# osbo_v11.net
KiCad netlist of a schematic drawn in EAGLE
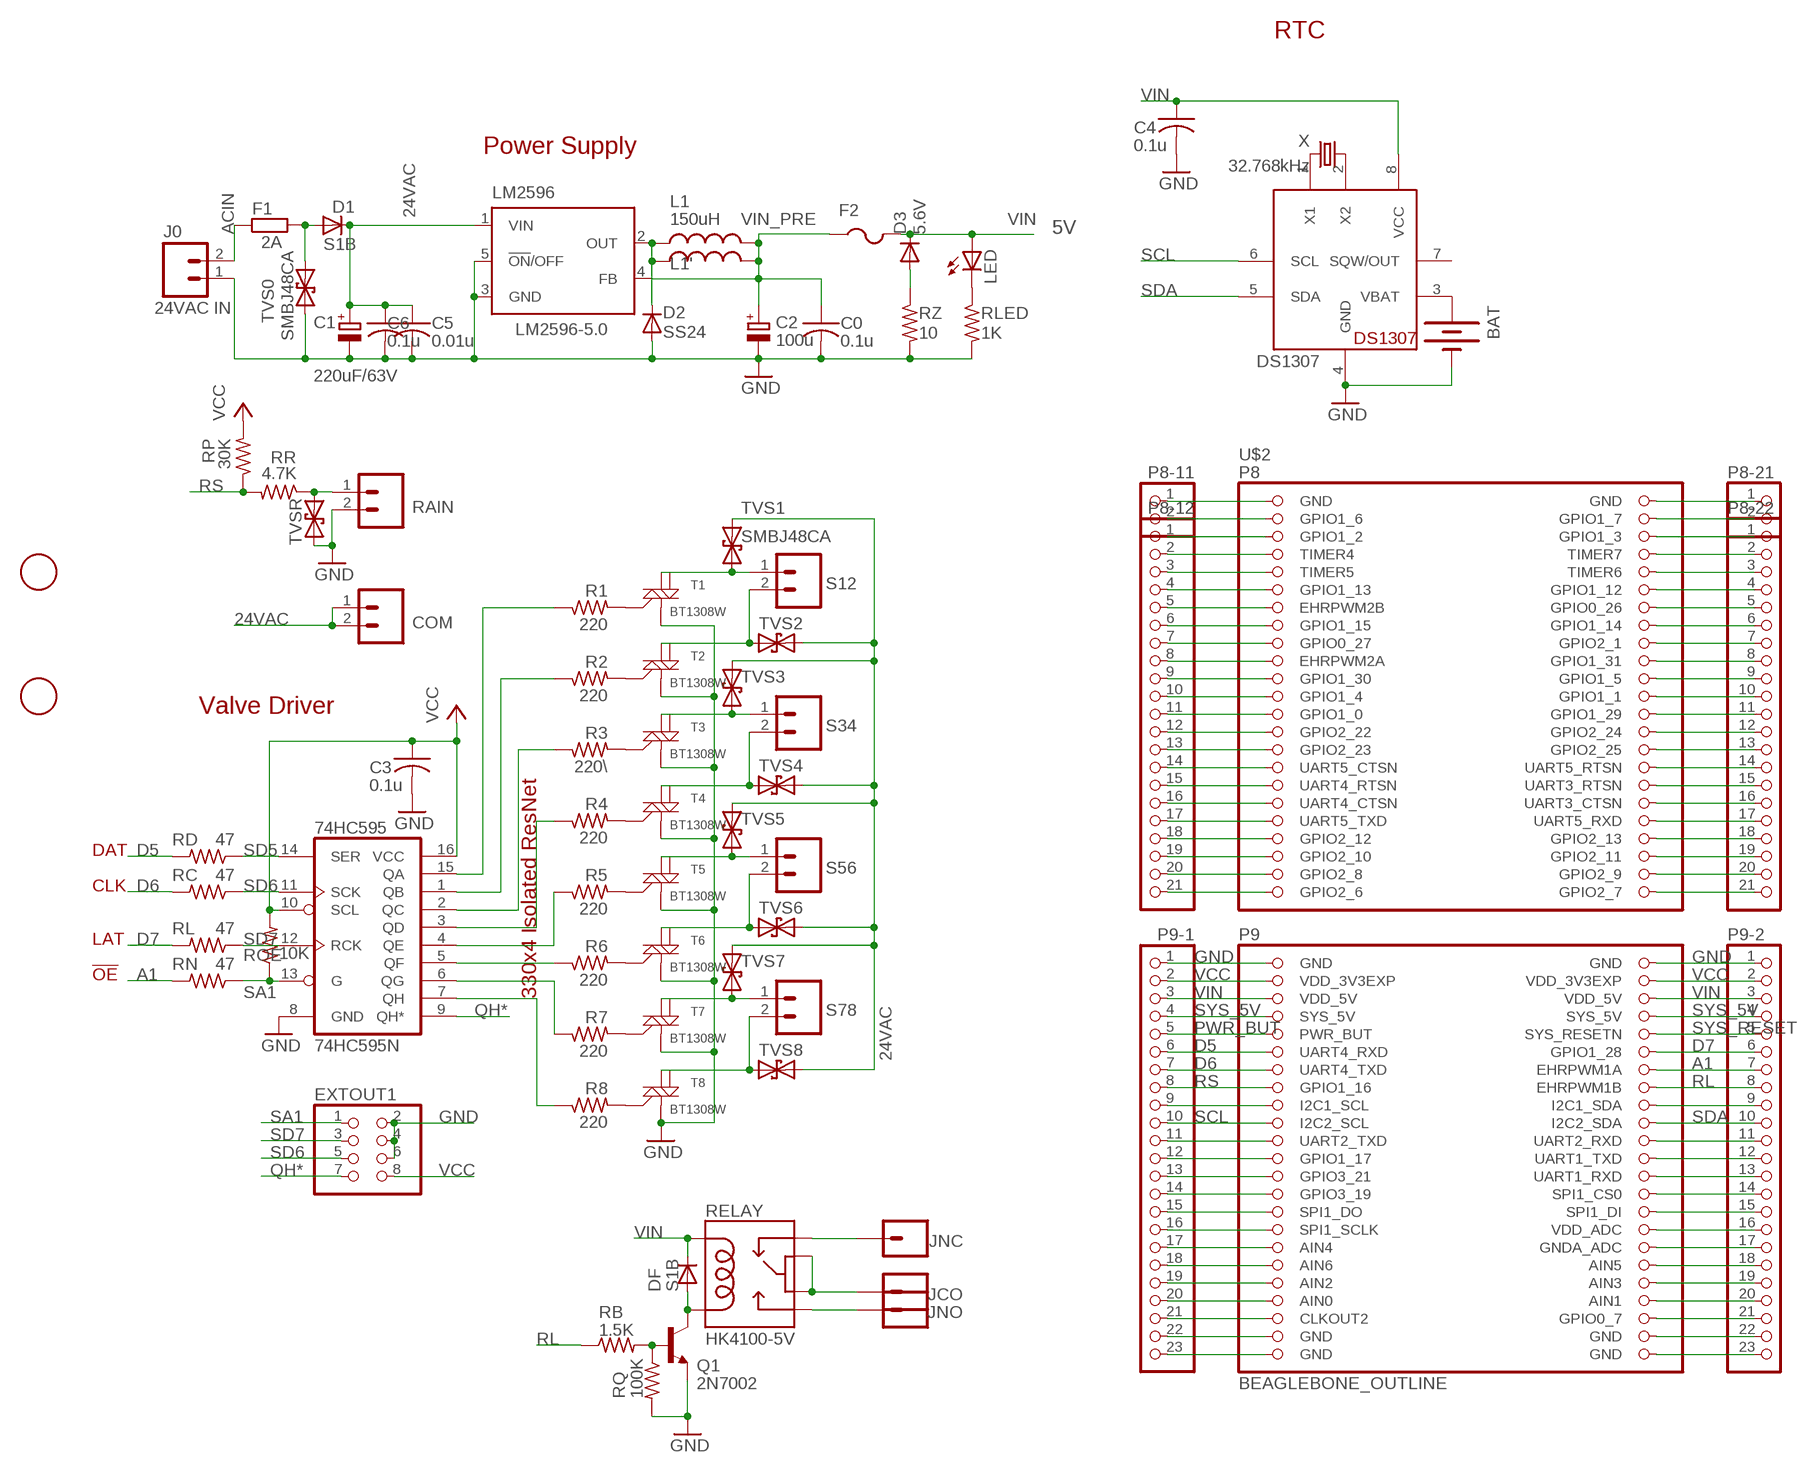
[diagram p0: schematic, sheet 1]

(export (version "E")
  (design (tool "Eeschema 10.0.6"))
  (components
    (comp (ref "74HC595")
      (value "74HC595N")
      (footprint "eagle-import:SO16")
      (libsource (lib "eagle-import") (part "74595DLS"))
    )
    (comp (ref "BAT")
      (value "BATTERYBATTERY_12MM_SMT")
      (footprint "eagle-import:BATTCON_12MM_SMT")
      (libsource (lib "eagle-import") (part "BATTERYBATTERY_12MM_SMT"))
    )
    (comp (ref "C0")
      (value "0.1u")
      (footprint "eagle-import:C0805K")
      (libsource (lib "eagle-import") (part "C-USC0805K"))
    )
    (comp (ref "C1")
      (value "220uF/63V")
      (footprint "eagle-import:E5-10.5-1")
      (libsource (lib "eagle-import") (part "CPOL-EUE5-10.5-1"))
    )
    (comp (ref "C2")
      (value "100u")
      (footprint "eagle-import:E3,5-8")
      (libsource (lib "eagle-import") (part "CPOL-EUE3.5-8"))
    )
    (comp (ref "C3")
      (value "0.1u")
      (footprint "eagle-import:C0805K")
      (libsource (lib "eagle-import") (part "C-USC0805K"))
    )
    (comp (ref "C4")
      (value "0.1u")
      (footprint "eagle-import:C0805K")
      (libsource (lib "eagle-import") (part "C-USC0805K"))
    )
    (comp (ref "C5")
      (value "0.01u")
      (footprint "eagle-import:C0805K")
      (libsource (lib "eagle-import") (part "C-USC0805K"))
    )
    (comp (ref "C6")
      (value "0.1u")
      (footprint "eagle-import:C0805K")
      (libsource (lib "eagle-import") (part "C-USC0805K"))
    )
    (comp (ref "COM")
      (value "M025MM-X")
      (footprint "eagle-import:SCREWTERMINAL-5MM-2-X")
      (libsource (lib "eagle-import") (part "M025MM-X"))
    )
    (comp (ref "D1")
      (value "S1B")
      (footprint "eagle-import:DO-214AC")
      (libsource (lib "eagle-import") (part "DIODE-DO-214AC"))
    )
    (comp (ref "D2")
      (value "SS24")
      (footprint "eagle-import:SMB")
      (libsource (lib "eagle-import") (part "DIODE-SMB"))
    )
    (comp (ref "D3")
      (value "5.6V")
      (footprint "eagle-import:MINIMELF")
      (libsource (lib "eagle-import") (part "DIODE-MINIMELF"))
    )
    (comp (ref "DF")
      (value "S1B")
      (footprint "eagle-import:DO-214AC")
      (libsource (lib "eagle-import") (part "DIODE-DO-214AC"))
    )
    (comp (ref "DS1307")
      (value "DS1307")
      (footprint "eagle-import:SO08")
      (libsource (lib "eagle-import") (part "DS1307SOIC"))
    )
    (comp (ref "EXTOUT1")
      (value "PINHD-2X4/90")
      (footprint "eagle-import:2X04_90")
      (libsource (lib "eagle-import") (part "PINHD-2X4/90"))
    )
    (comp (ref "F1")
      (value "2A")
      (footprint "eagle-import:0411V")
      (libsource (lib "eagle-import") (part "R-EU_0411/3V"))
    )
    (comp (ref "F2")
      (value "PTCFUSE-1812")
      (footprint "eagle-import:1812")
      (libsource (lib "eagle-import") (part "PTCFUSE-1812"))
    )
    (comp (ref "J0")
      (value "24VAC IN")
      (footprint "eagle-import:SCREWTERMINAL-4MM-2-X")
      (libsource (lib "eagle-import") (part "M024MM-X"))
    )
    (comp (ref "JCO")
      (value "M01PTH")
      (footprint "eagle-import:1X01")
      (libsource (lib "eagle-import") (part "M01PTH"))
    )
    (comp (ref "JNC")
      (value "M01PTH")
      (footprint "eagle-import:1X01")
      (libsource (lib "eagle-import") (part "M01PTH"))
    )
    (comp (ref "JNO")
      (value "M01PTH")
      (footprint "eagle-import:1X01")
      (libsource (lib "eagle-import") (part "M01PTH"))
    )
    (comp (ref "L1")
      (value "150uH")
      (footprint "eagle-import:CDRH125")
      (libsource (lib "eagle-import") (part "INDUCTORPWR"))
    )
    (comp (ref "L1'")
      (value "150uH")
      (footprint "eagle-import:0207_7")
      (libsource (lib "eagle-import") (part "L-US0207/7"))
    )
    (comp (ref "LED")
      (value "LEDCHIPLED_0805")
      (footprint "eagle-import:CHIPLED_0805")
      (libsource (lib "eagle-import") (part "LEDCHIPLED_0805"))
    )
    (comp (ref "LM2596")
      (value "LM2596-5.0")
      (footprint "eagle-import:TO263-5")
      (fields (field (name "MF") "NATIONAL SEMICONDUCTOR") (field (name "MPN") "LM2596S-ADJ/NOPB"))
      (libsource (lib "eagle-import") (part "LM2596S"))
    )
    (comp (ref "P8-11")
      (value "PINHD-1X2")
      (footprint "eagle-import:1X02")
      (libsource (lib "eagle-import") (part "PINHD-1X2"))
    )
    (comp (ref "P8-12")
      (value "PINHD-1X21")
      (footprint "eagle-import:1X21")
      (libsource (lib "eagle-import") (part "PINHD-1X21"))
    )
    (comp (ref "P8-21")
      (value "PINHD-1X2")
      (footprint "eagle-import:1X02")
      (libsource (lib "eagle-import") (part "PINHD-1X2"))
    )
    (comp (ref "P8-22")
      (value "PINHD-1X21")
      (footprint "eagle-import:1X21")
      (libsource (lib "eagle-import") (part "PINHD-1X21"))
    )
    (comp (ref "P9-1")
      (value "PINHD-1X23")
      (footprint "eagle-import:1X23")
      (libsource (lib "eagle-import") (part "PINHD-1X23"))
    )
    (comp (ref "P9-2")
      (value "PINHD-1X23")
      (footprint "eagle-import:1X23")
      (libsource (lib "eagle-import") (part "PINHD-1X23"))
    )
    (comp (ref "Q1")
      (value "2N7002")
      (footprint "eagle-import:SOT23-3")
      (libsource (lib "eagle-import") (part "TRANSISTOR_NPNSOT23-3"))
    )
    (comp (ref "R1")
      (value "220")
      (footprint "eagle-import:R0805")
      (libsource (lib "eagle-import") (part "R-US_R0805"))
    )
    (comp (ref "R2")
      (value "220")
      (footprint "eagle-import:R0805")
      (libsource (lib "eagle-import") (part "R-US_R0805"))
    )
    (comp (ref "R3")
      (value "220\\")
      (footprint "eagle-import:R0805")
      (libsource (lib "eagle-import") (part "R-US_R0805"))
    )
    (comp (ref "R4")
      (value "220")
      (footprint "eagle-import:R0805")
      (libsource (lib "eagle-import") (part "R-US_R0805"))
    )
    (comp (ref "R5")
      (value "220")
      (footprint "eagle-import:R0805")
      (libsource (lib "eagle-import") (part "R-US_R0805"))
    )
    (comp (ref "R6")
      (value "220")
      (footprint "eagle-import:R0805")
      (libsource (lib "eagle-import") (part "R-US_R0805"))
    )
    (comp (ref "R7")
      (value "220")
      (footprint "eagle-import:R0805")
      (libsource (lib "eagle-import") (part "R-US_R0805"))
    )
    (comp (ref "R8")
      (value "220")
      (footprint "eagle-import:R0805")
      (libsource (lib "eagle-import") (part "R-US_R0805"))
    )
    (comp (ref "RAIN")
      (value "M025MM-X")
      (footprint "eagle-import:SCREWTERMINAL-5MM-2-X")
      (libsource (lib "eagle-import") (part "M025MM-X"))
    )
    (comp (ref "RB")
      (value "1.5K")
      (footprint "eagle-import:R0805")
      (libsource (lib "eagle-import") (part "R-US_R0805"))
    )
    (comp (ref "RC")
      (value "47")
      (footprint "eagle-import:R0805")
      (libsource (lib "eagle-import") (part "R-US_R0805"))
    )
    (comp (ref "RD")
      (value "47")
      (footprint "eagle-import:R0805")
      (libsource (lib "eagle-import") (part "R-US_R0805"))
    )
    (comp (ref "RELAY")
      (value "HK4100-5V")
      (footprint "eagle-import:RELAY-HK4100F")
      (libsource (lib "eagle-import") (part "RELAY-2"))
    )
    (comp (ref "RL")
      (value "47")
      (footprint "eagle-import:R0805")
      (libsource (lib "eagle-import") (part "R-US_R0805"))
    )
    (comp (ref "RLED")
      (value "1K")
      (footprint "eagle-import:R0805")
      (libsource (lib "eagle-import") (part "R-US_R0805"))
    )
    (comp (ref "RN")
      (value "47")
      (footprint "eagle-import:R0805")
      (libsource (lib "eagle-import") (part "R-US_R0805"))
    )
    (comp (ref "ROE")
      (value "10K")
      (footprint "eagle-import:R0805")
      (libsource (lib "eagle-import") (part "R-US_R0805"))
    )
    (comp (ref "RP")
      (value "30K")
      (footprint "eagle-import:R0805")
      (libsource (lib "eagle-import") (part "R-US_R0805"))
    )
    (comp (ref "RQ")
      (value "100K")
      (footprint "eagle-import:R0805")
      (libsource (lib "eagle-import") (part "R-US_R0805"))
    )
    (comp (ref "RR")
      (value "4.7K")
      (footprint "eagle-import:R0805")
      (libsource (lib "eagle-import") (part "R-US_R0805"))
    )
    (comp (ref "RZ")
      (value "10")
      (footprint "eagle-import:R0805")
      (libsource (lib "eagle-import") (part "R-US_R0805"))
    )
    (comp (ref "S12")
      (value "M025MM-X")
      (footprint "eagle-import:SCREWTERMINAL-5MM-2-X")
      (libsource (lib "eagle-import") (part "M025MM-X"))
    )
    (comp (ref "S34")
      (value "M025MM-X")
      (footprint "eagle-import:SCREWTERMINAL-5MM-2-X")
      (libsource (lib "eagle-import") (part "M025MM-X"))
    )
    (comp (ref "S56")
      (value "M025MM-X")
      (footprint "eagle-import:SCREWTERMINAL-5MM-2-X")
      (libsource (lib "eagle-import") (part "M025MM-X"))
    )
    (comp (ref "S78")
      (value "M025MM-X")
      (footprint "eagle-import:SCREWTERMINAL-5MM-2-X")
      (libsource (lib "eagle-import") (part "M025MM-X"))
    )
    (comp (ref "T1")
      (value "BT1308W")
      (footprint "eagle-import:SOT223")
      (libsource (lib "eagle-import") (part "MAC97SOT223"))
    )
    (comp (ref "T2")
      (value "BT1308W")
      (footprint "eagle-import:SOT223")
      (libsource (lib "eagle-import") (part "MAC97SOT223"))
    )
    (comp (ref "T3")
      (value "BT1308W")
      (footprint "eagle-import:SOT223")
      (libsource (lib "eagle-import") (part "MAC97SOT223"))
    )
    (comp (ref "T4")
      (value "BT1308W")
      (footprint "eagle-import:SOT223")
      (libsource (lib "eagle-import") (part "MAC97SOT223"))
    )
    (comp (ref "T5")
      (value "BT1308W")
      (footprint "eagle-import:SOT223")
      (libsource (lib "eagle-import") (part "MAC97SOT223"))
    )
    (comp (ref "T6")
      (value "BT1308W")
      (footprint "eagle-import:SOT223")
      (libsource (lib "eagle-import") (part "MAC97SOT223"))
    )
    (comp (ref "T7")
      (value "BT1308W")
      (footprint "eagle-import:SOT223")
      (libsource (lib "eagle-import") (part "MAC97SOT223"))
    )
    (comp (ref "T8")
      (value "BT1308W")
      (footprint "eagle-import:SOT223")
      (libsource (lib "eagle-import") (part "MAC97SOT223"))
    )
    (comp (ref "TVS0")
      (value "SMBJ48CA")
      (footprint "eagle-import:SMB")
      (libsource (lib "eagle-import") (part "TVSSMB"))
    )
    (comp (ref "TVS1")
      (value "SMBJ48CA")
      (footprint "eagle-import:SMB")
      (libsource (lib "eagle-import") (part "TVSSMB"))
    )
    (comp (ref "TVS2")
      (value "TVSSMB")
      (footprint "eagle-import:SMB")
      (libsource (lib "eagle-import") (part "TVSSMB"))
    )
    (comp (ref "TVS3")
      (value "TVSSMB")
      (footprint "eagle-import:SMB")
      (libsource (lib "eagle-import") (part "TVSSMB"))
    )
    (comp (ref "TVS4")
      (value "TVSSMB")
      (footprint "eagle-import:SMB")
      (libsource (lib "eagle-import") (part "TVSSMB"))
    )
    (comp (ref "TVS5")
      (value "TVSSMB")
      (footprint "eagle-import:SMB")
      (libsource (lib "eagle-import") (part "TVSSMB"))
    )
    (comp (ref "TVS6")
      (value "TVSSMB")
      (footprint "eagle-import:SMB")
      (libsource (lib "eagle-import") (part "TVSSMB"))
    )
    (comp (ref "TVS7")
      (value "TVSSMB")
      (footprint "eagle-import:SMB")
      (libsource (lib "eagle-import") (part "TVSSMB"))
    )
    (comp (ref "TVS8")
      (value "TVSSMB")
      (footprint "eagle-import:SMB")
      (libsource (lib "eagle-import") (part "TVSSMB"))
    )
    (comp (ref "TVSR")
      (value "TVSSMB")
      (footprint "eagle-import:SMB")
      (libsource (lib "eagle-import") (part "TVSSMB"))
    )
    (comp (ref "U$1")
      (value "FIDUCIAL")
      (footprint "eagle-import:FIDUCIAL_1MM")
      (libsource (lib "eagle-import") (part "FIDUCIAL"))
    )
    (comp (ref "U$2")
      (value "BEAGLEBONE_OUTLINE")
      (footprint "eagle-import:BEAGLEBONE_SHIELD")
      (libsource (lib "eagle-import") (part "BEAGLEBONE_OUTLINE"))
    )
    (comp (ref "U$3")
      (value "FIDUCIAL")
      (footprint "eagle-import:FIDUCIAL_1MM")
      (libsource (lib "eagle-import") (part "FIDUCIAL"))
    )
    (comp (ref "X")
      (value "32.768kHz")
      (footprint "eagle-import:TC38H")
      (libsource (lib "eagle-import") (part "CRYSTALTC38H"))
    )
  )
  (nets
    (net (code "1") (name "/24VAC") (class "Default")
      (node (ref "COM") (pin "1") (pinfunction "1_1") (pintype "passive"))
      (node (ref "COM") (pin "2") (pinfunction "2_2") (pintype "passive"))
      (node (ref "D1") (pin "A") (pinfunction "A_A") (pintype "passive"))
      (node (ref "F1") (pin "2") (pinfunction "2_2") (pintype "passive"))
      (node (ref "TVS0") (pin "C") (pinfunction "C_C") (pintype "passive"))
      (node (ref "TVS1") (pin "C") (pinfunction "C_C") (pintype "passive"))
      (node (ref "TVS2") (pin "C") (pinfunction "C_C") (pintype "passive"))
      (node (ref "TVS3") (pin "C") (pinfunction "C_C") (pintype "passive"))
      (node (ref "TVS4") (pin "C") (pinfunction "C_C") (pintype "passive"))
      (node (ref "TVS5") (pin "C") (pinfunction "C_C") (pintype "passive"))
      (node (ref "TVS6") (pin "C") (pinfunction "C_C") (pintype "passive"))
      (node (ref "TVS7") (pin "C") (pinfunction "C_C") (pintype "passive"))
      (node (ref "TVS8") (pin "C") (pinfunction "C_C") (pintype "passive"))
    )
    (net (code "2") (name "/A1") (class "Default")
      (node (ref "P9-2") (pin "7") (pinfunction "7_7") (pintype "passive"))
      (node (ref "RN") (pin "2") (pinfunction "2_2") (pintype "passive"))
      (node (ref "U$2") (pin "60") (pinfunction "EHRPWM1A_60") (pintype "passive"))
    )
    (net (code "3") (name "/ACIN") (class "Default")
      (node (ref "F1") (pin "1") (pinfunction "1_1") (pintype "passive"))
      (node (ref "J0") (pin "2") (pinfunction "2_2") (pintype "passive"))
    )
    (net (code "4") (name "/D5") (class "Default")
      (node (ref "P9-1") (pin "6") (pinfunction "6_6") (pintype "passive"))
      (node (ref "RD") (pin "2") (pinfunction "2_2") (pintype "passive"))
      (node (ref "U$2") (pin "57") (pinfunction "UART4_RXD_57") (pintype "passive"))
    )
    (net (code "5") (name "/D6") (class "Default")
      (node (ref "P9-1") (pin "7") (pinfunction "7_7") (pintype "passive"))
      (node (ref "RC") (pin "2") (pinfunction "2_2") (pintype "passive"))
      (node (ref "U$2") (pin "59") (pinfunction "UART4_TXD_59") (pintype "passive"))
    )
    (net (code "6") (name "/D7") (class "Default")
      (node (ref "P9-2") (pin "6") (pinfunction "6_6") (pintype "passive"))
      (node (ref "RL") (pin "2") (pinfunction "2_2") (pintype "passive"))
      (node (ref "U$2") (pin "58") (pinfunction "GPIO1_28_58") (pintype "passive"))
    )
    (net (code "7") (name "/PWR_BUT") (class "Default")
      (node (ref "P9-1") (pin "5") (pinfunction "5_5") (pintype "passive"))
      (node (ref "U$2") (pin "55") (pinfunction "PWR_BUT_55") (pintype "passive"))
    )
    (net (code "8") (name "/QH*") (class "Default")
      (node (ref "74HC595") (pin "9") (pinfunction "QH*_9") (pintype "tri_state"))
      (node (ref "EXTOUT1") (pin "7") (pinfunction "7_7") (pintype "passive"))
    )
    (net (code "9") (name "/RL") (class "Default")
      (node (ref "P9-2") (pin "8") (pinfunction "8_8") (pintype "passive"))
      (node (ref "RB") (pin "1") (pinfunction "1_1") (pintype "passive"))
      (node (ref "U$2") (pin "62") (pinfunction "EHRPWM1B_62") (pintype "passive"))
    )
    (net (code "10") (name "/RS") (class "Default")
      (node (ref "P9-1") (pin "8") (pinfunction "8_8") (pintype "passive"))
      (node (ref "RP") (pin "1") (pinfunction "1_1") (pintype "passive"))
      (node (ref "RR") (pin "2") (pinfunction "2_2") (pintype "passive"))
      (node (ref "U$2") (pin "61") (pinfunction "GPIO1_16_61") (pintype "passive"))
    )
    (net (code "11") (name "/SA1") (class "Default")
      (node (ref "74HC595") (pin "13") (pinfunction "G_13") (pintype "input"))
      (node (ref "EXTOUT1") (pin "1") (pinfunction "1_1") (pintype "passive"))
      (node (ref "RN") (pin "1") (pinfunction "1_1") (pintype "passive"))
      (node (ref "ROE") (pin "1") (pinfunction "1_1") (pintype "passive"))
    )
    (net (code "12") (name "/SCL") (class "Default")
      (node (ref "DS1307") (pin "6") (pinfunction "SCL_6") (pintype "bidirectional"))
      (node (ref "P9-1") (pin "10") (pinfunction "10_10") (pintype "passive"))
      (node (ref "U$2") (pin "65") (pinfunction "I2C2_SCL_65") (pintype "passive"))
    )
    (net (code "13") (name "/SD5") (class "Default")
      (node (ref "74HC595") (pin "14") (pinfunction "SER_14") (pintype "input"))
      (node (ref "RD") (pin "1") (pinfunction "1_1") (pintype "passive"))
    )
    (net (code "14") (name "/SD6") (class "Default")
      (node (ref "74HC595") (pin "11") (pinfunction "SCK_11") (pintype "input"))
      (node (ref "EXTOUT1") (pin "5") (pinfunction "5_5") (pintype "passive"))
      (node (ref "RC") (pin "1") (pinfunction "1_1") (pintype "passive"))
    )
    (net (code "15") (name "/SD7") (class "Default")
      (node (ref "74HC595") (pin "12") (pinfunction "RCK_12") (pintype "input"))
      (node (ref "EXTOUT1") (pin "3") (pinfunction "3_3") (pintype "passive"))
      (node (ref "RL") (pin "1") (pinfunction "1_1") (pintype "passive"))
    )
    (net (code "16") (name "/SDA") (class "Default")
      (node (ref "DS1307") (pin "5") (pinfunction "SDA_5") (pintype "bidirectional"))
      (node (ref "P9-2") (pin "10") (pinfunction "10_10") (pintype "passive"))
      (node (ref "U$2") (pin "66") (pinfunction "I2C2_SDA_66") (pintype "passive"))
    )
    (net (code "17") (name "/SYS_5V") (class "Default")
      (node (ref "P9-1") (pin "4") (pinfunction "4_4") (pintype "passive"))
      (node (ref "P9-2") (pin "4") (pinfunction "4_4") (pintype "passive"))
      (node (ref "U$2") (pin "53") (pinfunction "SYS_5V_53") (pintype "power_in"))
      (node (ref "U$2") (pin "54") (pinfunction "SYS_5V_54") (pintype "passive"))
    )
    (net (code "18") (name "/SYS_RESET") (class "Default")
      (node (ref "P9-2") (pin "5") (pinfunction "5_5") (pintype "passive"))
      (node (ref "U$2") (pin "56") (pinfunction "SYS_RESETN_56") (pintype "passive"))
    )
    (net (code "19") (name "/VIN") (class "Default")
      (node (ref "C4") (pin "1") (pinfunction "1_1") (pintype "passive"))
      (node (ref "D3") (pin "C") (pinfunction "C_C") (pintype "passive"))
      (node (ref "DF") (pin "C") (pinfunction "C_C") (pintype "passive"))
      (node (ref "DS1307") (pin "8") (pinfunction "VCC_8") (pintype "power_in"))
      (node (ref "F2") (pin "2") (pinfunction "2_2") (pintype "passive"))
      (node (ref "LED") (pin "A") (pinfunction "A_A") (pintype "passive"))
      (node (ref "P9-1") (pin "3") (pinfunction "3_3") (pintype "passive"))
      (node (ref "P9-2") (pin "3") (pinfunction "3_3") (pintype "passive"))
      (node (ref "RELAY") (pin "2") (pinfunction "2_2") (pintype "bidirectional"))
      (node (ref "U$2") (pin "51") (pinfunction "VDD_5V_51") (pintype "power_in"))
      (node (ref "U$2") (pin "52") (pinfunction "VDD_5V_52") (pintype "power_in"))
    )
    (net (code "20") (name "/VIN_PRE") (class "Default")
      (node (ref "C0") (pin "1") (pinfunction "1_1") (pintype "passive"))
      (node (ref "C2") (pin "+") (pinfunction "+_+") (pintype "passive"))
      (node (ref "F2") (pin "1") (pinfunction "1_1") (pintype "passive"))
      (node (ref "L1") (pin "2") (pinfunction "2_2") (pintype "passive"))
      (node (ref "L1'") (pin "2") (pinfunction "2_2") (pintype "passive"))
      (node (ref "LM2596") (pin "4") (pinfunction "FB_4") (pintype "input"))
    )
    (net (code "21") (name "GND") (class "Default")
      (node (ref "74HC595") (pin "8") (pinfunction "GND_8") (pintype "power_in"))
      (node (ref "BAT") (pin "P$1") (pinfunction "-_P$1") (pintype "power_in"))
      (node (ref "C0") (pin "2") (pinfunction "2_2") (pintype "passive"))
      (node (ref "C1") (pin "-") (pinfunction "-_-") (pintype "passive"))
      (node (ref "C2") (pin "-") (pinfunction "-_-") (pintype "passive"))
      (node (ref "C3") (pin "2") (pinfunction "2_2") (pintype "passive"))
      (node (ref "C4") (pin "2") (pinfunction "2_2") (pintype "passive"))
      (node (ref "C5") (pin "2") (pinfunction "2_2") (pintype "passive"))
      (node (ref "C6") (pin "2") (pinfunction "2_2") (pintype "passive"))
      (node (ref "D2") (pin "A") (pinfunction "A_A") (pintype "passive"))
      (node (ref "DS1307") (pin "4") (pinfunction "GND_4") (pintype "power_in"))
      (node (ref "EXTOUT1") (pin "2") (pinfunction "2_2") (pintype "passive"))
      (node (ref "EXTOUT1") (pin "4") (pinfunction "4_4") (pintype "passive"))
      (node (ref "EXTOUT1") (pin "6") (pinfunction "6_6") (pintype "passive"))
      (node (ref "J0") (pin "1") (pinfunction "1_1") (pintype "passive"))
      (node (ref "LM2596") (pin "3") (pinfunction "GND_3") (pintype "power_in"))
      (node (ref "LM2596") (pin "5") (pinfunction "~{ON}/OFF_5") (pintype "input"))
      (node (ref "P8-11") (pin "1") (pinfunction "1_1") (pintype "passive"))
      (node (ref "P8-21") (pin "1") (pinfunction "1_1") (pintype "passive"))
      (node (ref "P9-1") (pin "1") (pinfunction "1_1") (pintype "passive"))
      (node (ref "P9-2") (pin "1") (pinfunction "1_1") (pintype "passive"))
      (node (ref "Q1") (pin "2") (pinfunction "E_2") (pintype "passive"))
      (node (ref "RAIN") (pin "2") (pinfunction "2_2") (pintype "passive"))
      (node (ref "RLED") (pin "2") (pinfunction "2_2") (pintype "passive"))
      (node (ref "RQ") (pin "2") (pinfunction "2_2") (pintype "passive"))
      (node (ref "RZ") (pin "2") (pinfunction "2_2") (pintype "passive"))
      (node (ref "T1") (pin "1") (pinfunction "M1_1") (pintype "bidirectional"))
      (node (ref "T2") (pin "1") (pinfunction "M1_1") (pintype "bidirectional"))
      (node (ref "T3") (pin "1") (pinfunction "M1_1") (pintype "bidirectional"))
      (node (ref "T4") (pin "1") (pinfunction "M1_1") (pintype "bidirectional"))
      (node (ref "T5") (pin "1") (pinfunction "M1_1") (pintype "bidirectional"))
      (node (ref "T6") (pin "1") (pinfunction "M1_1") (pintype "bidirectional"))
      (node (ref "T7") (pin "1") (pinfunction "M1_1") (pintype "bidirectional"))
      (node (ref "T8") (pin "1") (pinfunction "M1_1") (pintype "bidirectional"))
      (node (ref "TVS0") (pin "A") (pinfunction "A_A") (pintype "passive"))
      (node (ref "TVSR") (pin "A") (pinfunction "A_A") (pintype "passive"))
      (node (ref "U$2") (pin "1") (pinfunction "GND_1") (pintype "power_in"))
      (node (ref "U$2") (pin "2") (pinfunction "GND_2") (pintype "power_in"))
      (node (ref "U$2") (pin "47") (pinfunction "GND_47") (pintype "power_in"))
      (node (ref "U$2") (pin "48") (pinfunction "GND_48") (pintype "power_in"))
    )
    (net (code "22") (name "Net-(74HC595-QA)") (class "Default")
      (node (ref "74HC595") (pin "15") (pinfunction "QA_15") (pintype "tri_state"))
      (node (ref "R1") (pin "1") (pinfunction "1_1") (pintype "passive"))
    )
    (net (code "23") (name "Net-(74HC595-QB)") (class "Default")
      (node (ref "74HC595") (pin "1") (pinfunction "QB_1") (pintype "tri_state"))
      (node (ref "R2") (pin "1") (pinfunction "1_1") (pintype "passive"))
    )
    (net (code "24") (name "Net-(74HC595-QC)") (class "Default")
      (node (ref "74HC595") (pin "2") (pinfunction "QC_2") (pintype "tri_state"))
      (node (ref "R3") (pin "1") (pinfunction "1_1") (pintype "passive"))
    )
    (net (code "25") (name "Net-(74HC595-QD)") (class "Default")
      (node (ref "74HC595") (pin "3") (pinfunction "QD_3") (pintype "tri_state"))
      (node (ref "R4") (pin "1") (pinfunction "1_1") (pintype "passive"))
    )
    (net (code "26") (name "Net-(74HC595-QE)") (class "Default")
      (node (ref "74HC595") (pin "4") (pinfunction "QE_4") (pintype "tri_state"))
      (node (ref "R5") (pin "1") (pinfunction "1_1") (pintype "passive"))
    )
    (net (code "27") (name "Net-(74HC595-QF)") (class "Default")
      (node (ref "74HC595") (pin "5") (pinfunction "QF_5") (pintype "tri_state"))
      (node (ref "R6") (pin "1") (pinfunction "1_1") (pintype "passive"))
    )
    (net (code "28") (name "Net-(74HC595-QG)") (class "Default")
      (node (ref "74HC595") (pin "6") (pinfunction "QG_6") (pintype "tri_state"))
      (node (ref "R7") (pin "1") (pinfunction "1_1") (pintype "passive"))
    )
    (net (code "29") (name "Net-(74HC595-QH)") (class "Default")
      (node (ref "74HC595") (pin "7") (pinfunction "QH_7") (pintype "tri_state"))
      (node (ref "R8") (pin "1") (pinfunction "1_1") (pintype "passive"))
    )
    (net (code "30") (name "Net-(BAT-+)") (class "Default")
      (node (ref "BAT") (pin "P$2") (pinfunction "+_P$2") (pintype "power_in"))
      (node (ref "DS1307") (pin "3") (pinfunction "VBAT_3") (pintype "power_in"))
    )
    (net (code "31") (name "Net-(D3-PadA)") (class "Default")
      (node (ref "D3") (pin "A") (pinfunction "A_A") (pintype "passive"))
      (node (ref "RZ") (pin "1") (pinfunction "1_1") (pintype "passive"))
    )
    (net (code "32") (name "Net-(DS1307-X1)") (class "Default")
      (node (ref "DS1307") (pin "1") (pinfunction "X1_1") (pintype "passive"))
      (node (ref "X") (pin "2") (pinfunction "2_2") (pintype "passive"))
    )
    (net (code "33") (name "Net-(DS1307-X2)") (class "Default")
      (node (ref "DS1307") (pin "2") (pinfunction "X2_2") (pintype "passive"))
      (node (ref "X") (pin "1") (pinfunction "1_1") (pintype "passive"))
    )
    (net (code "34") (name "Net-(JCO-Pad1)") (class "Default")
      (node (ref "JCO") (pin "1") (pinfunction "1_1") (pintype "passive"))
      (node (ref "RELAY") (pin "5") (pinfunction "5_5") (pintype "bidirectional"))
      (node (ref "RELAY") (pin "6") (pinfunction "6_6") (pintype "bidirectional"))
    )
    (net (code "35") (name "Net-(JNC-Pad1)") (class "Default")
      (node (ref "JNC") (pin "1") (pinfunction "1_1") (pintype "passive"))
      (node (ref "RELAY") (pin "1") (pinfunction "1_1") (pintype "bidirectional"))
    )
    (net (code "36") (name "Net-(JNO-Pad1)") (class "Default")
      (node (ref "JNO") (pin "1") (pinfunction "1_1") (pintype "passive"))
      (node (ref "RELAY") (pin "10") (pinfunction "10_10") (pintype "bidirectional"))
    )
    (net (code "37") (name "Net-(LED-PadC)") (class "Default")
      (node (ref "LED") (pin "C") (pinfunction "C_C") (pintype "passive"))
      (node (ref "RLED") (pin "1") (pinfunction "1_1") (pintype "passive"))
    )
    (net (code "38") (name "Net-(LM2596-OUT)") (class "Default")
      (node (ref "D2") (pin "C") (pinfunction "C_C") (pintype "passive"))
      (node (ref "L1") (pin "1") (pinfunction "1_1") (pintype "passive"))
      (node (ref "L1'") (pin "1") (pinfunction "1_1") (pintype "passive"))
      (node (ref "LM2596") (pin "2") (pinfunction "OUT_2") (pintype "output"))
    )
    (net (code "39") (name "Net-(LM2596-VIN)") (class "Default")
      (node (ref "C1") (pin "+") (pinfunction "+_+") (pintype "passive"))
      (node (ref "C5") (pin "1") (pinfunction "1_1") (pintype "passive"))
      (node (ref "C6") (pin "1") (pinfunction "1_1") (pintype "passive"))
      (node (ref "D1") (pin "C") (pinfunction "C_C") (pintype "passive"))
      (node (ref "LM2596") (pin "1") (pinfunction "VIN_1") (pintype "input"))
    )
    (net (code "40") (name "Net-(P9-1-Pad22)") (class "Default")
      (node (ref "P9-1") (pin "22") (pinfunction "22_22") (pintype "passive"))
      (node (ref "U$2") (pin "89") (pinfunction "GND_89") (pintype "power_in"))
    )
    (net (code "41") (name "Net-(P9-1-Pad23)") (class "Default")
      (node (ref "P9-1") (pin "23") (pinfunction "23_23") (pintype "passive"))
      (node (ref "U$2") (pin "91") (pinfunction "GND_91") (pintype "power_in"))
    )
    (net (code "42") (name "Net-(P9-2-Pad22)") (class "Default")
      (node (ref "P9-2") (pin "22") (pinfunction "22_22") (pintype "passive"))
      (node (ref "U$2") (pin "90") (pinfunction "GND_90") (pintype "power_in"))
    )
    (net (code "43") (name "Net-(P9-2-Pad23)") (class "Default")
      (node (ref "P9-2") (pin "23") (pinfunction "23_23") (pintype "passive"))
      (node (ref "U$2") (pin "92") (pinfunction "GND_92") (pintype "power_in"))
    )
    (net (code "44") (name "Net-(Q1-B)") (class "Default")
      (node (ref "Q1") (pin "1") (pinfunction "B_1") (pintype "passive"))
      (node (ref "RB") (pin "2") (pinfunction "2_2") (pintype "passive"))
      (node (ref "RQ") (pin "1") (pinfunction "1_1") (pintype "passive"))
    )
    (net (code "45") (name "Net-(Q1-C)") (class "Default")
      (node (ref "DF") (pin "A") (pinfunction "A_A") (pintype "passive"))
      (node (ref "Q1") (pin "3") (pinfunction "C_3") (pintype "passive"))
      (node (ref "RELAY") (pin "9") (pinfunction "9_9") (pintype "bidirectional"))
    )
    (net (code "46") (name "Net-(RAIN-Pad1)") (class "Default")
      (node (ref "RAIN") (pin "1") (pinfunction "1_1") (pintype "passive"))
      (node (ref "RR") (pin "1") (pinfunction "1_1") (pintype "passive"))
      (node (ref "TVSR") (pin "C") (pinfunction "C_C") (pintype "passive"))
    )
    (net (code "47") (name "Net-(T1-G)") (class "Default")
      (node (ref "R1") (pin "2") (pinfunction "2_2") (pintype "passive"))
      (node (ref "T1") (pin "3") (pinfunction "G_3") (pintype "bidirectional"))
    )
    (net (code "48") (name "Net-(T1-M2)") (class "Default")
      (node (ref "S12") (pin "1") (pinfunction "1_1") (pintype "passive"))
      (node (ref "T1") (pin "2") (pinfunction "M2_2") (pintype "bidirectional"))
      (node (ref "TVS1") (pin "A") (pinfunction "A_A") (pintype "passive"))
    )
    (net (code "49") (name "Net-(T2-G)") (class "Default")
      (node (ref "R2") (pin "2") (pinfunction "2_2") (pintype "passive"))
      (node (ref "T2") (pin "3") (pinfunction "G_3") (pintype "bidirectional"))
    )
    (net (code "50") (name "Net-(T2-M2)") (class "Default")
      (node (ref "S12") (pin "2") (pinfunction "2_2") (pintype "passive"))
      (node (ref "T2") (pin "2") (pinfunction "M2_2") (pintype "bidirectional"))
      (node (ref "TVS2") (pin "A") (pinfunction "A_A") (pintype "passive"))
    )
    (net (code "51") (name "Net-(T3-G)") (class "Default")
      (node (ref "R3") (pin "2") (pinfunction "2_2") (pintype "passive"))
      (node (ref "T3") (pin "3") (pinfunction "G_3") (pintype "bidirectional"))
    )
    (net (code "52") (name "Net-(T3-M2)") (class "Default")
      (node (ref "S34") (pin "1") (pinfunction "1_1") (pintype "passive"))
      (node (ref "T3") (pin "2") (pinfunction "M2_2") (pintype "bidirectional"))
      (node (ref "TVS3") (pin "A") (pinfunction "A_A") (pintype "passive"))
    )
    (net (code "53") (name "Net-(T4-G)") (class "Default")
      (node (ref "R4") (pin "2") (pinfunction "2_2") (pintype "passive"))
      (node (ref "T4") (pin "3") (pinfunction "G_3") (pintype "bidirectional"))
    )
    (net (code "54") (name "Net-(T4-M2)") (class "Default")
      (node (ref "S34") (pin "2") (pinfunction "2_2") (pintype "passive"))
      (node (ref "T4") (pin "2") (pinfunction "M2_2") (pintype "bidirectional"))
      (node (ref "TVS4") (pin "A") (pinfunction "A_A") (pintype "passive"))
    )
    (net (code "55") (name "Net-(T5-G)") (class "Default")
      (node (ref "R5") (pin "2") (pinfunction "2_2") (pintype "passive"))
      (node (ref "T5") (pin "3") (pinfunction "G_3") (pintype "bidirectional"))
    )
    (net (code "56") (name "Net-(T5-M2)") (class "Default")
      (node (ref "S56") (pin "1") (pinfunction "1_1") (pintype "passive"))
      (node (ref "T5") (pin "2") (pinfunction "M2_2") (pintype "bidirectional"))
      (node (ref "TVS5") (pin "A") (pinfunction "A_A") (pintype "passive"))
    )
    (net (code "57") (name "Net-(T6-G)") (class "Default")
      (node (ref "R6") (pin "2") (pinfunction "2_2") (pintype "passive"))
      (node (ref "T6") (pin "3") (pinfunction "G_3") (pintype "bidirectional"))
    )
    (net (code "58") (name "Net-(T6-M2)") (class "Default")
      (node (ref "S56") (pin "2") (pinfunction "2_2") (pintype "passive"))
      (node (ref "T6") (pin "2") (pinfunction "M2_2") (pintype "bidirectional"))
      (node (ref "TVS6") (pin "A") (pinfunction "A_A") (pintype "passive"))
    )
    (net (code "59") (name "Net-(T7-G)") (class "Default")
      (node (ref "R7") (pin "2") (pinfunction "2_2") (pintype "passive"))
      (node (ref "T7") (pin "3") (pinfunction "G_3") (pintype "bidirectional"))
    )
    (net (code "60") (name "Net-(T7-M2)") (class "Default")
      (node (ref "S78") (pin "1") (pinfunction "1_1") (pintype "passive"))
      (node (ref "T7") (pin "2") (pinfunction "M2_2") (pintype "bidirectional"))
      (node (ref "TVS7") (pin "A") (pinfunction "A_A") (pintype "passive"))
    )
    (net (code "61") (name "Net-(T8-G)") (class "Default")
      (node (ref "R8") (pin "2") (pinfunction "2_2") (pintype "passive"))
      (node (ref "T8") (pin "3") (pinfunction "G_3") (pintype "bidirectional"))
    )
    (net (code "62") (name "Net-(T8-M2)") (class "Default")
      (node (ref "S78") (pin "2") (pinfunction "2_2") (pintype "passive"))
      (node (ref "T8") (pin "2") (pinfunction "M2_2") (pintype "bidirectional"))
      (node (ref "TVS8") (pin "A") (pinfunction "A_A") (pintype "passive"))
    )
    (net (code "63") (name "Net-(U$2-AIN0)") (class "Default")
      (node (ref "P9-1") (pin "20") (pinfunction "20_20") (pintype "passive"))
      (node (ref "U$2") (pin "85") (pinfunction "AIN0_85") (pintype "power_in"))
    )
    (net (code "64") (name "Net-(U$2-AIN1)") (class "Default")
      (node (ref "P9-2") (pin "20") (pinfunction "20_20") (pintype "passive"))
      (node (ref "U$2") (pin "86") (pinfunction "AIN1_86") (pintype "passive"))
    )
    (net (code "65") (name "Net-(U$2-AIN2)") (class "Default")
      (node (ref "P9-1") (pin "19") (pinfunction "19_19") (pintype "passive"))
      (node (ref "U$2") (pin "83") (pinfunction "AIN2_83") (pintype "passive"))
    )
    (net (code "66") (name "Net-(U$2-AIN3)") (class "Default")
      (node (ref "P9-2") (pin "19") (pinfunction "19_19") (pintype "passive"))
      (node (ref "U$2") (pin "84") (pinfunction "AIN3_84") (pintype "passive"))
    )
    (net (code "67") (name "Net-(U$2-AIN4)") (class "Default")
      (node (ref "P9-1") (pin "17") (pinfunction "17_17") (pintype "passive"))
      (node (ref "U$2") (pin "79") (pinfunction "AIN4_79") (pintype "passive"))
    )
    (net (code "68") (name "Net-(U$2-AIN5)") (class "Default")
      (node (ref "P9-2") (pin "18") (pinfunction "18_18") (pintype "passive"))
      (node (ref "U$2") (pin "82") (pinfunction "AIN5_82") (pintype "passive"))
    )
    (net (code "69") (name "Net-(U$2-AIN6)") (class "Default")
      (node (ref "P9-1") (pin "18") (pinfunction "18_18") (pintype "passive"))
      (node (ref "U$2") (pin "81") (pinfunction "AIN6_81") (pintype "passive"))
    )
    (net (code "70") (name "Net-(U$2-CLKOUT2)") (class "Default")
      (node (ref "P9-1") (pin "21") (pinfunction "21_21") (pintype "passive"))
      (node (ref "U$2") (pin "87") (pinfunction "CLKOUT2_87") (pintype "input"))
    )
    (net (code "71") (name "Net-(U$2-EHRPWM2A)") (class "Default")
      (node (ref "P8-12") (pin "8") (pinfunction "8_8") (pintype "passive"))
      (node (ref "U$2") (pin "19") (pinfunction "EHRPWM2A_19") (pintype "passive"))
    )
    (net (code "72") (name "Net-(U$2-EHRPWM2B)") (class "Default")
      (node (ref "P8-12") (pin "5") (pinfunction "5_5") (pintype "passive"))
      (node (ref "U$2") (pin "13") (pinfunction "EHRPWM2B_13") (pintype "passive"))
    )
    (net (code "73") (name "Net-(U$2-GNDA_ADC)") (class "Default")
      (node (ref "P9-2") (pin "17") (pinfunction "17_17") (pintype "passive"))
      (node (ref "U$2") (pin "80") (pinfunction "GNDA_ADC_80") (pintype "passive"))
    )
    (net (code "74") (name "Net-(U$2-GPIO0_7)") (class "Default")
      (node (ref "P9-2") (pin "21") (pinfunction "21_21") (pintype "passive"))
      (node (ref "U$2") (pin "88") (pinfunction "GPIO0_7_88") (pintype "passive"))
    )
    (net (code "75") (name "Net-(U$2-GPIO0_26)") (class "Default")
      (node (ref "P8-22") (pin "5") (pinfunction "5_5") (pintype "passive"))
      (node (ref "U$2") (pin "14") (pinfunction "GPIO0_26_14") (pintype "passive"))
    )
    (net (code "76") (name "Net-(U$2-GPIO0_27)") (class "Default")
      (node (ref "P8-12") (pin "7") (pinfunction "7_7") (pintype "passive"))
      (node (ref "U$2") (pin "17") (pinfunction "GPIO0_27_17") (pintype "passive"))
    )
    (net (code "77") (name "Net-(U$2-GPIO1_0)") (class "Default")
      (node (ref "P8-12") (pin "11") (pinfunction "11_11") (pintype "passive"))
      (node (ref "U$2") (pin "25") (pinfunction "GPIO1_0_25") (pintype "passive"))
    )
    (net (code "78") (name "Net-(U$2-GPIO1_1)") (class "Default")
      (node (ref "P8-22") (pin "10") (pinfunction "10_10") (pintype "passive"))
      (node (ref "U$2") (pin "24") (pinfunction "GPIO1_1_24") (pintype "passive"))
    )
    (net (code "79") (name "Net-(U$2-GPIO1_2)") (class "Default")
      (node (ref "P8-12") (pin "1") (pinfunction "1_1") (pintype "passive"))
      (node (ref "U$2") (pin "5") (pinfunction "GPIO1_2_5") (pintype "passive"))
    )
    (net (code "80") (name "Net-(U$2-GPIO1_3)") (class "Default")
      (node (ref "P8-22") (pin "1") (pinfunction "1_1") (pintype "passive"))
      (node (ref "U$2") (pin "6") (pinfunction "GPIO1_3_6") (pintype "passive"))
    )
    (net (code "81") (name "Net-(U$2-GPIO1_4)") (class "Default")
      (node (ref "P8-12") (pin "10") (pinfunction "10_10") (pintype "passive"))
      (node (ref "U$2") (pin "23") (pinfunction "GPIO1_4_23") (pintype "passive"))
    )
    (net (code "82") (name "Net-(U$2-GPIO1_5)") (class "Default")
      (node (ref "P8-22") (pin "9") (pinfunction "9_9") (pintype "passive"))
      (node (ref "U$2") (pin "22") (pinfunction "GPIO1_5_22") (pintype "passive"))
    )
    (net (code "83") (name "Net-(U$2-GPIO1_6)") (class "Default")
      (node (ref "P8-11") (pin "2") (pinfunction "2_2") (pintype "passive"))
      (node (ref "U$2") (pin "3") (pinfunction "GPIO1_6_3") (pintype "passive"))
    )
    (net (code "84") (name "Net-(U$2-GPIO1_7)") (class "Default")
      (node (ref "P8-21") (pin "2") (pinfunction "2_2") (pintype "passive"))
      (node (ref "U$2") (pin "4") (pinfunction "GPIO1_7_4") (pintype "passive"))
    )
    (net (code "85") (name "Net-(U$2-GPIO1_12)") (class "Default")
      (node (ref "P8-22") (pin "4") (pinfunction "4_4") (pintype "passive"))
      (node (ref "U$2") (pin "12") (pinfunction "GPIO1_12_12") (pintype "passive"))
    )
    (net (code "86") (name "Net-(U$2-GPIO1_13)") (class "Default")
      (node (ref "P8-12") (pin "4") (pinfunction "4_4") (pintype "passive"))
      (node (ref "U$2") (pin "11") (pinfunction "GPIO1_13_11") (pintype "passive"))
    )
    (net (code "87") (name "Net-(U$2-GPIO1_14)") (class "Default")
      (node (ref "P8-22") (pin "6") (pinfunction "6_6") (pintype "passive"))
      (node (ref "U$2") (pin "16") (pinfunction "GPIO1_14_16") (pintype "passive"))
    )
    (net (code "88") (name "Net-(U$2-GPIO1_15)") (class "Default")
      (node (ref "P8-12") (pin "6") (pinfunction "6_6") (pintype "passive"))
      (node (ref "U$2") (pin "15") (pinfunction "GPIO1_15_15") (pintype "passive"))
    )
    (net (code "89") (name "Net-(U$2-GPIO1_17)") (class "Default")
      (node (ref "P9-1") (pin "12") (pinfunction "12_12") (pintype "passive"))
      (node (ref "U$2") (pin "69") (pinfunction "GPIO1_17_69") (pintype "passive"))
    )
    (net (code "90") (name "Net-(U$2-GPIO1_29)") (class "Default")
      (node (ref "P8-22") (pin "11") (pinfunction "11_11") (pintype "passive"))
      (node (ref "U$2") (pin "26") (pinfunction "GPIO1_29_26") (pintype "passive"))
    )
    (net (code "91") (name "Net-(U$2-GPIO1_30)") (class "Default")
      (node (ref "P8-12") (pin "9") (pinfunction "9_9") (pintype "passive"))
      (node (ref "U$2") (pin "21") (pinfunction "GPIO1_30_21") (pintype "passive"))
    )
    (net (code "92") (name "Net-(U$2-GPIO1_31)") (class "Default")
      (node (ref "P8-22") (pin "8") (pinfunction "8_8") (pintype "passive"))
      (node (ref "U$2") (pin "20") (pinfunction "GPIO1_31_20") (pintype "passive"))
    )
    (net (code "93") (name "Net-(U$2-GPIO2_1)") (class "Default")
      (node (ref "P8-22") (pin "7") (pinfunction "7_7") (pintype "passive"))
      (node (ref "U$2") (pin "18") (pinfunction "GPIO2_1_18") (pintype "passive"))
    )
    (net (code "94") (name "Net-(U$2-GPIO2_6)") (class "Default")
      (node (ref "P8-12") (pin "21") (pinfunction "21_21") (pintype "passive"))
      (node (ref "U$2") (pin "45") (pinfunction "GPIO2_6_45") (pintype "passive"))
    )
    (net (code "95") (name "Net-(U$2-GPIO2_7)") (class "Default")
      (node (ref "P8-22") (pin "21") (pinfunction "21_21") (pintype "passive"))
      (node (ref "U$2") (pin "46") (pinfunction "GPIO2_7_46") (pintype "passive"))
    )
    (net (code "96") (name "Net-(U$2-GPIO2_8)") (class "Default")
      (node (ref "P8-12") (pin "20") (pinfunction "20_20") (pintype "passive"))
      (node (ref "U$2") (pin "43") (pinfunction "GPIO2_8_43") (pintype "passive"))
    )
    (net (code "97") (name "Net-(U$2-GPIO2_9)") (class "Default")
      (node (ref "P8-22") (pin "20") (pinfunction "20_20") (pintype "passive"))
      (node (ref "U$2") (pin "44") (pinfunction "GPIO2_9_44") (pintype "passive"))
    )
    (net (code "98") (name "Net-(U$2-GPIO2_10)") (class "Default")
      (node (ref "P8-12") (pin "19") (pinfunction "19_19") (pintype "passive"))
      (node (ref "U$2") (pin "41") (pinfunction "GPIO2_10_41") (pintype "passive"))
    )
    (net (code "99") (name "Net-(U$2-GPIO2_11)") (class "Default")
      (node (ref "P8-22") (pin "19") (pinfunction "19_19") (pintype "passive"))
      (node (ref "U$2") (pin "42") (pinfunction "GPIO2_11_42") (pintype "passive"))
    )
    (net (code "100") (name "Net-(U$2-GPIO2_12)") (class "Default")
      (node (ref "P8-12") (pin "18") (pinfunction "18_18") (pintype "passive"))
      (node (ref "U$2") (pin "39") (pinfunction "GPIO2_12_39") (pintype "passive"))
    )
    (net (code "101") (name "Net-(U$2-GPIO2_13)") (class "Default")
      (node (ref "P8-22") (pin "18") (pinfunction "18_18") (pintype "passive"))
      (node (ref "U$2") (pin "40") (pinfunction "GPIO2_13_40") (pintype "passive"))
    )
    (net (code "102") (name "Net-(U$2-GPIO2_22)") (class "Default")
      (node (ref "P8-12") (pin "12") (pinfunction "12_12") (pintype "passive"))
      (node (ref "U$2") (pin "27") (pinfunction "GPIO2_22_27") (pintype "passive"))
    )
    (net (code "103") (name "Net-(U$2-GPIO2_23)") (class "Default")
      (node (ref "P8-12") (pin "13") (pinfunction "13_13") (pintype "passive"))
      (node (ref "U$2") (pin "29") (pinfunction "GPIO2_23_29") (pintype "passive"))
    )
    (net (code "104") (name "Net-(U$2-GPIO2_24)") (class "Default")
      (node (ref "P8-22") (pin "12") (pinfunction "12_12") (pintype "passive"))
      (node (ref "U$2") (pin "28") (pinfunction "GPIO2_24_28") (pintype "passive"))
    )
    (net (code "105") (name "Net-(U$2-GPIO2_25)") (class "Default")
      (node (ref "P8-22") (pin "13") (pinfunction "13_13") (pintype "passive"))
      (node (ref "U$2") (pin "30") (pinfunction "GPIO2_25_30") (pintype "passive"))
    )
    (net (code "106") (name "Net-(U$2-GPIO3_19)") (class "Default")
      (node (ref "P9-1") (pin "14") (pinfunction "14_14") (pintype "passive"))
      (node (ref "U$2") (pin "73") (pinfunction "GPIO3_19_73") (pintype "passive"))
    )
    (net (code "107") (name "Net-(U$2-GPIO3_21)") (class "Default")
      (node (ref "P9-1") (pin "13") (pinfunction "13_13") (pintype "passive"))
      (node (ref "U$2") (pin "71") (pinfunction "GPIO3_21_71") (pintype "passive"))
    )
    (net (code "108") (name "Net-(U$2-I2C1_SCL)") (class "Default")
      (node (ref "P9-1") (pin "9") (pinfunction "9_9") (pintype "passive"))
      (node (ref "U$2") (pin "63") (pinfunction "I2C1_SCL_63") (pintype "passive"))
    )
    (net (code "109") (name "Net-(U$2-I2C1_SDA)") (class "Default")
      (node (ref "P9-2") (pin "9") (pinfunction "9_9") (pintype "passive"))
      (node (ref "U$2") (pin "64") (pinfunction "I2C1_SDA_64") (pintype "passive"))
    )
    (net (code "110") (name "Net-(U$2-SPI1_CS0)") (class "Default")
      (node (ref "P9-2") (pin "14") (pinfunction "14_14") (pintype "passive"))
      (node (ref "U$2") (pin "74") (pinfunction "SPI1_CS0_74") (pintype "passive"))
    )
    (net (code "111") (name "Net-(U$2-SPI1_DI)") (class "Default")
      (node (ref "P9-2") (pin "15") (pinfunction "15_15") (pintype "passive"))
      (node (ref "U$2") (pin "76") (pinfunction "SPI1_DI_76") (pintype "passive"))
    )
    (net (code "112") (name "Net-(U$2-SPI1_DO)") (class "Default")
      (node (ref "P9-1") (pin "15") (pinfunction "15_15") (pintype "passive"))
      (node (ref "U$2") (pin "75") (pinfunction "SPI1_DO_75") (pintype "passive"))
    )
    (net (code "113") (name "Net-(U$2-SPI1_SCLK)") (class "Default")
      (node (ref "P9-1") (pin "16") (pinfunction "16_16") (pintype "passive"))
      (node (ref "U$2") (pin "77") (pinfunction "SPI1_SCLK_77") (pintype "passive"))
    )
    (net (code "114") (name "Net-(U$2-TIMER4)") (class "Default")
      (node (ref "P8-12") (pin "2") (pinfunction "2_2") (pintype "passive"))
      (node (ref "U$2") (pin "7") (pinfunction "TIMER4_7") (pintype "passive"))
    )
    (net (code "115") (name "Net-(U$2-TIMER5)") (class "Default")
      (node (ref "P8-12") (pin "3") (pinfunction "3_3") (pintype "passive"))
      (node (ref "U$2") (pin "9") (pinfunction "TIMER5_9") (pintype "passive"))
    )
    (net (code "116") (name "Net-(U$2-TIMER6)") (class "Default")
      (node (ref "P8-22") (pin "3") (pinfunction "3_3") (pintype "passive"))
      (node (ref "U$2") (pin "10") (pinfunction "TIMER6_10") (pintype "passive"))
    )
    (net (code "117") (name "Net-(U$2-TIMER7)") (class "Default")
      (node (ref "P8-22") (pin "2") (pinfunction "2_2") (pintype "passive"))
      (node (ref "U$2") (pin "8") (pinfunction "TIMER7_8") (pintype "passive"))
    )
    (net (code "118") (name "Net-(U$2-UART1_RXD)") (class "Default")
      (node (ref "P9-2") (pin "13") (pinfunction "13_13") (pintype "passive"))
      (node (ref "U$2") (pin "72") (pinfunction "UART1_RXD_72") (pintype "passive"))
    )
    (net (code "119") (name "Net-(U$2-UART1_TXD)") (class "Default")
      (node (ref "P9-2") (pin "12") (pinfunction "12_12") (pintype "passive"))
      (node (ref "U$2") (pin "70") (pinfunction "UART1_TXD_70") (pintype "passive"))
    )
    (net (code "120") (name "Net-(U$2-UART2_RXD)") (class "Default")
      (node (ref "P9-2") (pin "11") (pinfunction "11_11") (pintype "passive"))
      (node (ref "U$2") (pin "68") (pinfunction "UART2_RXD_68") (pintype "passive"))
    )
    (net (code "121") (name "Net-(U$2-UART2_TXD)") (class "Default")
      (node (ref "P9-1") (pin "11") (pinfunction "11_11") (pintype "passive"))
      (node (ref "U$2") (pin "67") (pinfunction "UART2_TXD_67") (pintype "passive"))
    )
    (net (code "122") (name "Net-(U$2-UART3_CTSN)") (class "Default")
      (node (ref "P8-22") (pin "16") (pinfunction "16_16") (pintype "passive"))
      (node (ref "U$2") (pin "36") (pinfunction "UART3_CTSN_36") (pintype "passive"))
    )
    (net (code "123") (name "Net-(U$2-UART3_RTSN)") (class "Default")
      (node (ref "P8-22") (pin "15") (pinfunction "15_15") (pintype "passive"))
      (node (ref "U$2") (pin "34") (pinfunction "UART3_RTSN_34") (pintype "passive"))
    )
    (net (code "124") (name "Net-(U$2-UART4_CTSN)") (class "Default")
      (node (ref "P8-12") (pin "16") (pinfunction "16_16") (pintype "passive"))
      (node (ref "U$2") (pin "35") (pinfunction "UART4_CTSN_35") (pintype "passive"))
    )
    (net (code "125") (name "Net-(U$2-UART4_RTSN)") (class "Default")
      (node (ref "P8-12") (pin "15") (pinfunction "15_15") (pintype "passive"))
      (node (ref "U$2") (pin "33") (pinfunction "UART4_RTSN_33") (pintype "passive"))
    )
    (net (code "126") (name "Net-(U$2-UART5_CTSN)") (class "Default")
      (node (ref "P8-12") (pin "14") (pinfunction "14_14") (pintype "passive"))
      (node (ref "U$2") (pin "31") (pinfunction "UART5_CTSN_31") (pintype "passive"))
    )
    (net (code "127") (name "Net-(U$2-UART5_RTSN)") (class "Default")
      (node (ref "P8-22") (pin "14") (pinfunction "14_14") (pintype "passive"))
      (node (ref "U$2") (pin "32") (pinfunction "UART5_RTSN_32") (pintype "passive"))
    )
    (net (code "128") (name "Net-(U$2-UART5_RXD)") (class "Default")
      (node (ref "P8-22") (pin "17") (pinfunction "17_17") (pintype "passive"))
      (node (ref "U$2") (pin "38") (pinfunction "UART5_RXD_38") (pintype "passive"))
    )
    (net (code "129") (name "Net-(U$2-UART5_TXD)") (class "Default")
      (node (ref "P8-12") (pin "17") (pinfunction "17_17") (pintype "passive"))
      (node (ref "U$2") (pin "37") (pinfunction "UART5_TXD_37") (pintype "passive"))
    )
    (net (code "130") (name "Net-(U$2-VDD_ADC)") (class "Default")
      (node (ref "P9-2") (pin "16") (pinfunction "16_16") (pintype "passive"))
      (node (ref "U$2") (pin "78") (pinfunction "VDD_ADC_78") (pintype "passive"))
    )
    (net (code "131") (name "VCC") (class "Default")
      (node (ref "74HC595") (pin "10") (pinfunction "SCL_10") (pintype "input"))
      (node (ref "74HC595") (pin "16") (pinfunction "VCC_16") (pintype "power_in"))
      (node (ref "C3") (pin "1") (pinfunction "1_1") (pintype "passive"))
      (node (ref "EXTOUT1") (pin "8") (pinfunction "8_8") (pintype "passive"))
      (node (ref "P9-1") (pin "2") (pinfunction "2_2") (pintype "passive"))
      (node (ref "P9-2") (pin "2") (pinfunction "2_2") (pintype "passive"))
      (node (ref "ROE") (pin "2") (pinfunction "2_2") (pintype "passive"))
      (node (ref "RP") (pin "2") (pinfunction "2_2") (pintype "passive"))
      (node (ref "U$2") (pin "49") (pinfunction "VDD_3V3EXP_49") (pintype "power_in"))
      (node (ref "U$2") (pin "50") (pinfunction "VDD_3V3EXP_50") (pintype "power_in"))
    )
    (net (code "132") (name "unconnected-(DS1307-SQW{slash}OUT-Pad7)") (class "Default")
      (node (ref "DS1307") (pin "7") (pinfunction "SQW/OUT_7") (pintype "bidirectional"))
    )
    (net (code "133") (name "unconnected-(T1-M2-4-Pad4)") (class "Default")
      (node (ref "T1") (pin "4") (pinfunction "M2-4_4") (pintype "bidirectional"))
    )
    (net (code "134") (name "unconnected-(T2-M2-4-Pad4)") (class "Default")
      (node (ref "T2") (pin "4") (pinfunction "M2-4_4") (pintype "bidirectional"))
    )
    (net (code "135") (name "unconnected-(T3-M2-4-Pad4)") (class "Default")
      (node (ref "T3") (pin "4") (pinfunction "M2-4_4") (pintype "bidirectional"))
    )
    (net (code "136") (name "unconnected-(T4-M2-4-Pad4)") (class "Default")
      (node (ref "T4") (pin "4") (pinfunction "M2-4_4") (pintype "bidirectional"))
    )
    (net (code "137") (name "unconnected-(T5-M2-4-Pad4)") (class "Default")
      (node (ref "T5") (pin "4") (pinfunction "M2-4_4") (pintype "bidirectional"))
    )
    (net (code "138") (name "unconnected-(T6-M2-4-Pad4)") (class "Default")
      (node (ref "T6") (pin "4") (pinfunction "M2-4_4") (pintype "bidirectional"))
    )
    (net (code "139") (name "unconnected-(T7-M2-4-Pad4)") (class "Default")
      (node (ref "T7") (pin "4") (pinfunction "M2-4_4") (pintype "bidirectional"))
    )
    (net (code "140") (name "unconnected-(T8-M2-4-Pad4)") (class "Default")
      (node (ref "T8") (pin "4") (pinfunction "M2-4_4") (pintype "bidirectional"))
    )
  )
)
